# ST-Link-V1_0.net
KiCad netlist of a schematic drawn in Altium Designer
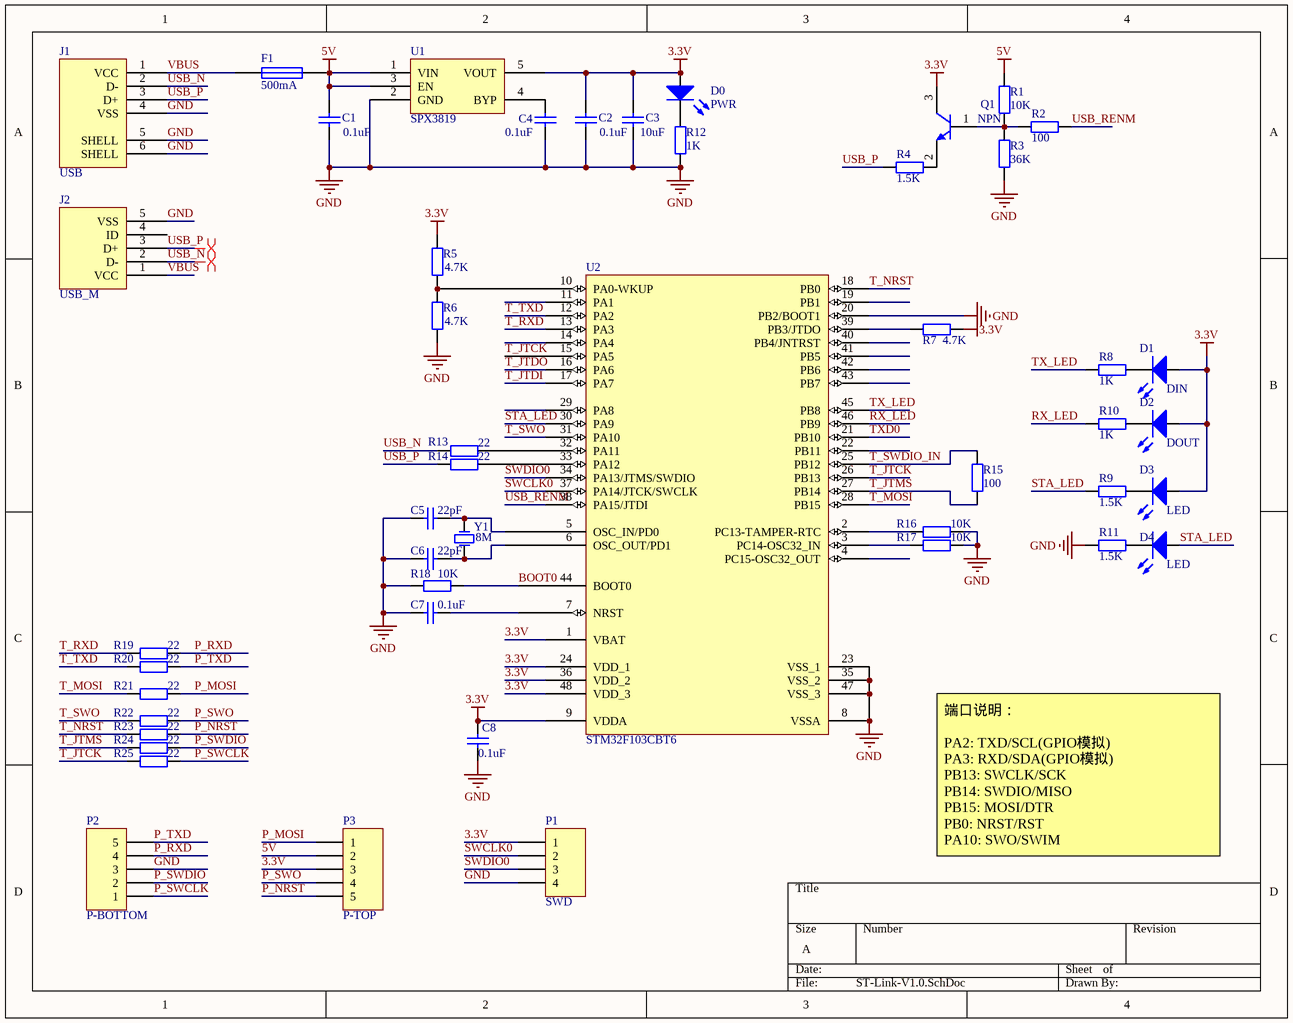
[diagram p0: ST-Link-V1.0.SchDoc]

(export (version "E")
  (design (tool "Eeschema 10.0.6"))
  (components
    (comp (ref "C1")
      (value "0.1uF")
      (footprint "C-0603")
      (description "Capacitor")
      (fields (field (name "Comment") "Cap") (field (name "PUBLISHER") "Altium Limited"))
      (libsource (lib "Miscellaneous Devices") (part "Cap"))
    )
    (comp (ref "C2")
      (value "0.1uF")
      (footprint "C-0603")
      (description "Capacitor")
      (fields (field (name "Comment") "Cap") (field (name "PUBLISHER") "Altium Limited"))
      (libsource (lib "Miscellaneous Devices") (part "Cap"))
    )
    (comp (ref "C3")
      (value "10uF")
      (footprint "C-0603")
      (description "Capacitor")
      (fields (field (name "Comment") "Cap") (field (name "PUBLISHER") "Altium Limited"))
      (libsource (lib "Miscellaneous Devices") (part "Cap"))
    )
    (comp (ref "C4")
      (value "0.1uF")
      (footprint "C-0603")
      (description "Capacitor")
      (fields (field (name "Comment") "Cap") (field (name "PUBLISHER") "Altium Limited"))
      (libsource (lib "Miscellaneous Devices") (part "Cap"))
    )
    (comp (ref "C5")
      (value "22pF")
      (footprint "C-0603")
      (fields (field (name "Comment") "Cap"))
      (libsource (lib "WK_PCB") (part "Cap"))
    )
    (comp (ref "C6")
      (value "22pF")
      (footprint "C-0603")
      (fields (field (name "Comment") "Cap"))
      (libsource (lib "WK_PCB") (part "Cap"))
    )
    (comp (ref "C7")
      (value "0.1uF")
      (footprint "C-0603")
      (fields (field (name "Comment") "Cap"))
      (libsource (lib "WK_PCB") (part "Cap"))
    )
    (comp (ref "C8")
      (value "0.1uF")
      (footprint "C-0603")
      (description "Capacitor")
      (fields (field (name "Comment") "Cap") (field (name "PUBLISHER") "Altium Limited"))
      (libsource (lib "Miscellaneous Devices") (part "Cap"))
    )
    (comp (ref "D0")
      (value "PWR")
      (footprint "SMT_LED_0603")
      (description "Typical RED, GREEN, YELLOW, AMBER GaAs LED")
      (fields (field (name "PUBLISHER") "Altium Limited"))
      (libsource (lib "ST-Link-V2.2") (part "LED2"))
    )
    (comp (ref "D1")
      (value "DIN")
      (footprint "SMT_LED_0603")
      (description "Typical RED, GREEN, YELLOW, AMBER GaAs LED")
      (fields (field (name "PUBLISHER") "Altium Limited"))
      (libsource (lib "ST-Link-V2.2") (part "LED2"))
    )
    (comp (ref "D2")
      (value "DOUT")
      (footprint "SMT_LED_0603")
      (description "Typical RED, GREEN, YELLOW, AMBER GaAs LED")
      (fields (field (name "PUBLISHER") "Altium Limited"))
      (libsource (lib "ST-Link-V2.2") (part "LED2"))
    )
    (comp (ref "D3")
      (value "LED")
      (footprint "SMT_LED_0603")
      (description "Typical RED, GREEN, YELLOW, AMBER GaAs LED")
      (fields (field (name "PUBLISHER") "Altium Limited"))
      (libsource (lib "ST-Link-V2.2") (part "LED2"))
    )
    (comp (ref "D4")
      (value "LED")
      (footprint "SMT_LED_0603")
      (description "Typical RED, GREEN, YELLOW, AMBER GaAs LED")
      (fields (field (name "PUBLISHER") "Altium Limited"))
      (libsource (lib "ST-Link-V2.2") (part "LED2"))
    )
    (comp (ref "F1")
      (value "500mA")
      (footprint "0805-1")
      (description "保险丝")
      (fields (field (name "Comment") "Fuse1"))
      (libsource (lib "ST-Link-V2.2") (part "Fuse1"))
    )
    (comp (ref "J1")
      (value "USB")
      (footprint "USB-B")
      (description "USB接口")
      (libsource (lib "HDR_Fszhang") (part "USB"))
    )
    (comp (ref "J2")
      (value "USB_M")
      (footprint "USB_MICRO_5S_B")
      (description "Micro/Mini USB")
      (libsource (lib "HDR_Fszhang") (part "USB_M"))
    )
    (comp (ref "P1")
      (value "SWD")
      (footprint "SIP4-1.27")
      (description "Header, 4-Pin")
      (fields (field (name "PUBLISHER") "Altium Limited"))
      (libsource (lib "Miscellaneous Connectors") (part "Header 4"))
    )
    (comp (ref "P2")
      (value "P-BOTTOM")
      (footprint "HEADER_5")
      (description "Header, 5-Pin")
      (fields (field (name "PUBLISHER") "Altium Limited"))
      (libsource (lib "Miscellaneous Connectors") (part "Header 5"))
    )
    (comp (ref "P3")
      (value "P-TOP")
      (footprint "HEADER_5")
      (description "Header, 5-Pin")
      (fields (field (name "PUBLISHER") "Altium Limited"))
      (libsource (lib "") (part "Header 5_1"))
    )
    (comp (ref "Q1")
      (value "NPN")
      (footprint "SOT23-3")
      (description "贴片三极管")
      (fields (field (name "PUBLISHER") "Altium Limited"))
      (libsource (lib "Fszhang") (part "NPN1"))
    )
    (comp (ref "R1")
      (value "10K")
      (footprint "0603-1")
      (description "贴片电阻")
      (fields (field (name "Comment") "Res1") (field (name "PUBLISHER") "Altium Limited"))
      (libsource (lib "Fszhang") (part "Res1"))
    )
    (comp (ref "R2")
      (value "100")
      (footprint "0603-1")
      (description "贴片电阻")
      (fields (field (name "Comment") "Res1") (field (name "PUBLISHER") "Altium Limited"))
      (libsource (lib "") (part "Res1_1"))
    )
    (comp (ref "R3")
      (value "36K")
      (footprint "0603-1")
      (description "贴片电阻")
      (fields (field (name "Comment") "Res1") (field (name "PUBLISHER") "Altium Limited"))
      (libsource (lib "Fszhang") (part "Res1"))
    )
    (comp (ref "R4")
      (value "1.5K")
      (footprint "0603-1")
      (description "贴片电阻")
      (fields (field (name "Comment") "Res1") (field (name "PUBLISHER") "Altium Limited"))
      (libsource (lib "") (part "Res1_2"))
    )
    (comp (ref "R5")
      (value "4.7K")
      (footprint "0603-1")
      (description "Resistor")
      (fields (field (name "Comment") "Res2") (field (name "PUBLISHER") "Altium Limited"))
      (libsource (lib "") (part "Res2_2"))
    )
    (comp (ref "R6")
      (value "4.7K")
      (footprint "0603-1")
      (description "Resistor")
      (fields (field (name "Comment") "Res2") (field (name "PUBLISHER") "Altium Limited"))
      (libsource (lib "") (part "Res2_2"))
    )
    (comp (ref "R7")
      (value "4.7K")
      (footprint "0603-1")
      (description "Resistor")
      (fields (field (name "Comment") "Res2") (field (name "PUBLISHER") "Altium Limited"))
      (libsource (lib "Miscellaneous Devices") (part "Res2"))
    )
    (comp (ref "R8")
      (value "1K")
      (footprint "0603-1")
      (description "Resistor")
      (fields (field (name "Comment") "Res2") (field (name "PUBLISHER") "Altium Limited"))
      (libsource (lib "Miscellaneous Devices") (part "Res2"))
    )
    (comp (ref "R9")
      (value "1.5K")
      (footprint "0603-1")
      (description "Resistor")
      (fields (field (name "Comment") "Res2") (field (name "PUBLISHER") "Altium Limited"))
      (libsource (lib "") (part "Res2_1"))
    )
    (comp (ref "R10")
      (value "1K")
      (footprint "0603-1")
      (description "Resistor")
      (fields (field (name "Comment") "Res2") (field (name "PUBLISHER") "Altium Limited"))
      (libsource (lib "Miscellaneous Devices") (part "Res2"))
    )
    (comp (ref "R11")
      (value "1.5K")
      (footprint "0603-1")
      (description "Resistor")
      (fields (field (name "Comment") "Res2") (field (name "PUBLISHER") "Altium Limited"))
      (libsource (lib "") (part "Res2_2"))
    )
    (comp (ref "R12")
      (value "1K")
      (footprint "0603-1")
      (description "Resistor")
      (fields (field (name "Comment") "Res2") (field (name "PUBLISHER") "Altium Limited"))
      (libsource (lib "") (part "Res2_2"))
    )
    (comp (ref "R13")
      (value "22")
      (footprint "0603-1")
      (description "Resistor")
      (fields (field (name "Comment") "Res2") (field (name "PUBLISHER") "Altium Limited"))
      (libsource (lib "Miscellaneous Devices") (part "Res2"))
    )
    (comp (ref "R14")
      (value "22")
      (footprint "0603-1")
      (description "Resistor")
      (fields (field (name "Comment") "Res2") (field (name "PUBLISHER") "Altium Limited"))
      (libsource (lib "Miscellaneous Devices") (part "Res2"))
    )
    (comp (ref "R15")
      (value "100")
      (footprint "0603-1")
      (description "Resistor")
      (fields (field (name "Comment") "Res2") (field (name "PUBLISHER") "Altium Limited"))
      (libsource (lib "") (part "Res2_2"))
    )
    (comp (ref "R16")
      (value "10K")
      (footprint "0603-1")
      (description "贴片电阻")
      (fields (field (name "Comment") "Res1") (field (name "PUBLISHER") "Altium Limited"))
      (libsource (lib "") (part "Res1_1"))
    )
    (comp (ref "R17")
      (value "10K")
      (footprint "0603-1")
      (description "贴片电阻")
      (fields (field (name "Comment") "Res1") (field (name "PUBLISHER") "Altium Limited"))
      (libsource (lib "") (part "Res1_1"))
    )
    (comp (ref "R18")
      (value "10K")
      (footprint "0603-1")
      (description "Resistor")
      (fields (field (name "Comment") "Res2") (field (name "PUBLISHER") "Altium Limited"))
      (libsource (lib "Miscellaneous Devices") (part "Res2"))
    )
    (comp (ref "R19")
      (value "22")
      (footprint "0603-1")
      (description "Resistor")
      (fields (field (name "Comment") "Res2") (field (name "PUBLISHER") "Altium Limited"))
      (libsource (lib "Miscellaneous Devices") (part "Res2"))
    )
    (comp (ref "R20")
      (value "22")
      (footprint "0603-1")
      (description "Resistor")
      (fields (field (name "Comment") "Res2") (field (name "PUBLISHER") "Altium Limited"))
      (libsource (lib "Miscellaneous Devices") (part "Res2"))
    )
    (comp (ref "R21")
      (value "22")
      (footprint "0603-1")
      (description "Resistor")
      (fields (field (name "Comment") "Res2") (field (name "PUBLISHER") "Altium Limited"))
      (libsource (lib "Miscellaneous Devices") (part "Res2"))
    )
    (comp (ref "R22")
      (value "22")
      (footprint "0603-1")
      (description "Resistor")
      (fields (field (name "Comment") "Res2") (field (name "PUBLISHER") "Altium Limited"))
      (libsource (lib "Miscellaneous Devices") (part "Res2"))
    )
    (comp (ref "R23")
      (value "22")
      (footprint "0603-1")
      (description "Resistor")
      (fields (field (name "Comment") "Res2") (field (name "PUBLISHER") "Altium Limited"))
      (libsource (lib "Miscellaneous Devices") (part "Res2"))
    )
    (comp (ref "R24")
      (value "22")
      (footprint "0603-1")
      (description "Resistor")
      (fields (field (name "Comment") "Res2") (field (name "PUBLISHER") "Altium Limited"))
      (libsource (lib "Miscellaneous Devices") (part "Res2"))
    )
    (comp (ref "R25")
      (value "22")
      (footprint "0603-1")
      (description "Resistor")
      (fields (field (name "Comment") "Res2") (field (name "PUBLISHER") "Altium Limited"))
      (libsource (lib "Miscellaneous Devices") (part "Res2"))
    )
    (comp (ref "U1") (value "SPX3819") (footprint "SOT23-5") (libsource (lib "Schlib1") (part "SPX3819")))
    (comp (ref "U2")
      (value "STM32F103CBT6")
      (footprint "LQFP48_N")
      (description "STM32 ARM-based 32-bit MCU with 64 Kbytes Flash, 48-pin LQFP, Industrial Temperature")
      (fields (field (name "PUBLISHER") "Altium Limited"))
      (libsource (lib "ST Microcontroller 32-Bit STM32") (part "STM32F103C8T6"))
    )
    (comp (ref "Y1")
      (value "8M")
      (footprint "XAL5032 2-Leads")
      (description "Crystal Oscillator")
      (fields
        (field (name "MANUFACTURER") "Generic Components")
        (field (name "PUBLISHER") "Altium Hobart Technology Centre")
      )
      (libsource (lib "*") (part "XTAL"))
    )
  )
  (nets
    (net (code "1") (name "/BOOT0") (class "Default")
      (node (ref "R18") (pin "2") (pinfunction "2_2") (pintype "passive"))
      (node (ref "U2") (pin "44") (pinfunction "BOOT0_44") (pintype "passive"))
    )
    (net (code "2") (name "/P_MOSI") (class "Default")
      (node (ref "P3") (pin "1") (pinfunction "1_1") (pintype "passive"))
      (node (ref "R21") (pin "2") (pinfunction "2_2") (pintype "passive"))
    )
    (net (code "3") (name "/P_NRST") (class "Default")
      (node (ref "P3") (pin "5") (pinfunction "5_5") (pintype "passive"))
      (node (ref "R23") (pin "2") (pinfunction "2_2") (pintype "passive"))
    )
    (net (code "4") (name "/P_RXD") (class "Default")
      (node (ref "P2") (pin "4") (pinfunction "4_4") (pintype "passive"))
      (node (ref "R19") (pin "2") (pinfunction "2_2") (pintype "passive"))
    )
    (net (code "5") (name "/P_SWCLK") (class "Default")
      (node (ref "P2") (pin "1") (pinfunction "1_1") (pintype "passive"))
      (node (ref "R25") (pin "2") (pinfunction "2_2") (pintype "passive"))
    )
    (net (code "6") (name "/P_SWDIO") (class "Default")
      (node (ref "P2") (pin "2") (pinfunction "2_2") (pintype "passive"))
      (node (ref "R24") (pin "2") (pinfunction "2_2") (pintype "passive"))
    )
    (net (code "7") (name "/P_SWO") (class "Default")
      (node (ref "P3") (pin "4") (pinfunction "4_4") (pintype "passive"))
      (node (ref "R22") (pin "2") (pinfunction "2_2") (pintype "passive"))
    )
    (net (code "8") (name "/P_TXD") (class "Default")
      (node (ref "P2") (pin "5") (pinfunction "5_5") (pintype "passive"))
      (node (ref "R20") (pin "2") (pinfunction "2_2") (pintype "passive"))
    )
    (net (code "9") (name "/RX_LED") (class "Default")
      (node (ref "R10") (pin "1") (pinfunction "1_1") (pintype "passive"))
      (node (ref "U2") (pin "46") (pinfunction "PB9_46") (pintype "bidirectional"))
    )
    (net (code "10") (name "/STA_LED") (class "Default")
      (node (ref "D4") (pin "1") (pinfunction "A_1") (pintype "passive"))
      (node (ref "R9") (pin "2") (pinfunction "2_2") (pintype "passive"))
      (node (ref "U2") (pin "30") (pinfunction "PA9_30") (pintype "bidirectional"))
    )
    (net (code "11") (name "/SWCLK0") (class "Default")
      (node (ref "P1") (pin "2") (pinfunction "2_2") (pintype "passive"))
      (node (ref "U2") (pin "37") (pinfunction "PA14/JTCK/SWCLK_37") (pintype "bidirectional"))
    )
    (net (code "12") (name "/SWDIO0") (class "Default")
      (node (ref "P1") (pin "3") (pinfunction "3_3") (pintype "passive"))
      (node (ref "U2") (pin "34") (pinfunction "PA13/JTMS/SWDIO_34") (pintype "bidirectional"))
    )
    (net (code "13") (name "/TXD0") (class "Default")
      (node (ref "U2") (pin "21") (pinfunction "PB10_21") (pintype "bidirectional"))
    )
    (net (code "14") (name "/TX_LED") (class "Default")
      (node (ref "R8") (pin "1") (pinfunction "1_1") (pintype "passive"))
      (node (ref "U2") (pin "45") (pinfunction "PB8_45") (pintype "bidirectional"))
    )
    (net (code "15") (name "/T_JTCK") (class "Default")
      (node (ref "R25") (pin "1") (pinfunction "1_1") (pintype "passive"))
      (node (ref "U2") (pin "15") (pinfunction "PA5_15") (pintype "bidirectional"))
      (node (ref "U2") (pin "26") (pinfunction "PB13_26") (pintype "bidirectional"))
    )
    (net (code "16") (name "/T_JTDI") (class "Default")
      (node (ref "U2") (pin "17") (pinfunction "PA7_17") (pintype "bidirectional"))
    )
    (net (code "17") (name "/T_JTDO") (class "Default")
      (node (ref "U2") (pin "16") (pinfunction "PA6_16") (pintype "bidirectional"))
    )
    (net (code "18") (name "/T_JTMS") (class "Default")
      (node (ref "R15") (pin "1") (pinfunction "1_1") (pintype "passive"))
      (node (ref "R24") (pin "1") (pinfunction "1_1") (pintype "passive"))
      (node (ref "U2") (pin "27") (pinfunction "PB14_27") (pintype "bidirectional"))
    )
    (net (code "19") (name "/T_MOSI") (class "Default")
      (node (ref "R21") (pin "1") (pinfunction "1_1") (pintype "passive"))
      (node (ref "U2") (pin "28") (pinfunction "PB15_28") (pintype "bidirectional"))
    )
    (net (code "20") (name "/T_NRST") (class "Default")
      (node (ref "R23") (pin "1") (pinfunction "1_1") (pintype "passive"))
      (node (ref "U2") (pin "18") (pinfunction "PB0_18") (pintype "bidirectional"))
    )
    (net (code "21") (name "/T_RXD") (class "Default")
      (node (ref "R19") (pin "1") (pinfunction "1_1") (pintype "passive"))
      (node (ref "U2") (pin "13") (pinfunction "PA3_13") (pintype "bidirectional"))
    )
    (net (code "22") (name "/T_SWDIO_IN") (class "Default")
      (node (ref "R15") (pin "2") (pinfunction "2_2") (pintype "passive"))
      (node (ref "U2") (pin "25") (pinfunction "PB12_25") (pintype "bidirectional"))
    )
    (net (code "23") (name "/T_SWO") (class "Default")
      (node (ref "R22") (pin "1") (pinfunction "1_1") (pintype "passive"))
      (node (ref "U2") (pin "31") (pinfunction "PA10_31") (pintype "bidirectional"))
    )
    (net (code "24") (name "/T_TXD") (class "Default")
      (node (ref "R20") (pin "1") (pinfunction "1_1") (pintype "passive"))
      (node (ref "U2") (pin "12") (pinfunction "PA2_12") (pintype "bidirectional"))
    )
    (net (code "25") (name "/USB_N") (class "Default")
      (node (ref "J1") (pin "2") (pinfunction "D-_2") (pintype "passive"))
      (node (ref "J2") (pin "2") (pinfunction "D-_2") (pintype "passive"))
      (node (ref "R13") (pin "1") (pinfunction "1_1") (pintype "passive"))
    )
    (net (code "26") (name "/USB_P") (class "Default")
      (node (ref "J1") (pin "3") (pinfunction "D+_3") (pintype "passive"))
      (node (ref "J2") (pin "3") (pinfunction "D+_3") (pintype "passive"))
      (node (ref "R14") (pin "1") (pinfunction "1_1") (pintype "passive"))
      (node (ref "R4") (pin "2") (pinfunction "2_2") (pintype "passive"))
    )
    (net (code "27") (name "/USB_RENM") (class "Default")
      (node (ref "R2") (pin "2") (pinfunction "2_2") (pintype "passive"))
      (node (ref "U2") (pin "38") (pinfunction "PA15/JTDI_38") (pintype "bidirectional"))
    )
    (net (code "28") (name "/VBUS") (class "Default")
      (node (ref "F1") (pin "1") (pinfunction "1_1") (pintype "passive"))
      (node (ref "J1") (pin "1") (pinfunction "VCC_1") (pintype "passive"))
      (node (ref "J2") (pin "1") (pinfunction "VCC_1") (pintype "passive"))
    )
    (net (code "29") (name "3.3V") (class "Default")
      (node (ref "C2") (pin "2") (pinfunction "2_2") (pintype "passive"))
      (node (ref "C3") (pin "2") (pinfunction "2_2") (pintype "passive"))
      (node (ref "C8") (pin "2") (pinfunction "2_2") (pintype "passive"))
      (node (ref "D0") (pin "1") (pinfunction "A_1") (pintype "passive"))
      (node (ref "D1") (pin "1") (pinfunction "A_1") (pintype "passive"))
      (node (ref "D2") (pin "1") (pinfunction "A_1") (pintype "passive"))
      (node (ref "D3") (pin "1") (pinfunction "A_1") (pintype "passive"))
      (node (ref "P1") (pin "1") (pinfunction "1_1") (pintype "passive"))
      (node (ref "P3") (pin "3") (pinfunction "3_3") (pintype "passive"))
      (node (ref "Q1") (pin "3") (pinfunction "C_3") (pintype "passive"))
      (node (ref "R5") (pin "2") (pinfunction "2_2") (pintype "passive"))
      (node (ref "R7") (pin "2") (pinfunction "2_2") (pintype "passive"))
      (node (ref "U1") (pin "5") (pinfunction "VOUT_5") (pintype "passive"))
      (node (ref "U2") (pin "1") (pinfunction "VBAT_1") (pintype "power_in"))
      (node (ref "U2") (pin "24") (pinfunction "VDD_1_24") (pintype "power_in"))
      (node (ref "U2") (pin "36") (pinfunction "VDD_2_36") (pintype "power_in"))
      (node (ref "U2") (pin "48") (pinfunction "VDD_3_48") (pintype "power_in"))
      (node (ref "U2") (pin "9") (pinfunction "VDDA_9") (pintype "power_in"))
    )
    (net (code "30") (name "5V") (class "Default")
      (node (ref "C1") (pin "2") (pinfunction "2_2") (pintype "passive"))
      (node (ref "F1") (pin "2") (pinfunction "2_2") (pintype "passive"))
      (node (ref "P3") (pin "2") (pinfunction "2_2") (pintype "passive"))
      (node (ref "R1") (pin "1") (pinfunction "1_1") (pintype "passive"))
      (node (ref "U1") (pin "1") (pinfunction "VIN_1") (pintype "passive"))
      (node (ref "U1") (pin "3") (pinfunction "EN_3") (pintype "passive"))
    )
    (net (code "31") (name "GND") (class "Default")
      (node (ref "C1") (pin "1") (pinfunction "1_1") (pintype "passive"))
      (node (ref "C2") (pin "1") (pinfunction "1_1") (pintype "passive"))
      (node (ref "C3") (pin "1") (pinfunction "1_1") (pintype "passive"))
      (node (ref "C4") (pin "1") (pinfunction "1_1") (pintype "passive"))
      (node (ref "C5") (pin "1") (pinfunction "1_1") (pintype "passive"))
      (node (ref "C6") (pin "1") (pinfunction "1_1") (pintype "passive"))
      (node (ref "C7") (pin "1") (pinfunction "1_1") (pintype "passive"))
      (node (ref "C8") (pin "1") (pinfunction "1_1") (pintype "passive"))
      (node (ref "J1") (pin "4") (pinfunction "VSS_4") (pintype "passive"))
      (node (ref "J1") (pin "5") (pinfunction "SHELL_5") (pintype "passive"))
      (node (ref "J1") (pin "6") (pinfunction "SHELL_6") (pintype "passive"))
      (node (ref "J2") (pin "5") (pinfunction "VSS_5") (pintype "passive"))
      (node (ref "P1") (pin "4") (pinfunction "4_4") (pintype "passive"))
      (node (ref "P2") (pin "3") (pinfunction "3_3") (pintype "passive"))
      (node (ref "R11") (pin "1") (pinfunction "1_1") (pintype "passive"))
      (node (ref "R12") (pin "1") (pinfunction "1_1") (pintype "passive"))
      (node (ref "R16") (pin "2") (pinfunction "2_2") (pintype "passive"))
      (node (ref "R17") (pin "2") (pinfunction "2_2") (pintype "passive"))
      (node (ref "R18") (pin "1") (pinfunction "1_1") (pintype "passive"))
      (node (ref "R3") (pin "2") (pinfunction "2_2") (pintype "passive"))
      (node (ref "R6") (pin "1") (pinfunction "1_1") (pintype "passive"))
      (node (ref "U1") (pin "2") (pinfunction "GND_2") (pintype "passive"))
      (node (ref "U2") (pin "20") (pinfunction "PB2/BOOT1_20") (pintype "bidirectional"))
      (node (ref "U2") (pin "23") (pinfunction "VSS_1_23") (pintype "power_in"))
      (node (ref "U2") (pin "35") (pinfunction "VSS_2_35") (pintype "power_in"))
      (node (ref "U2") (pin "47") (pinfunction "VSS_3_47") (pintype "power_in"))
      (node (ref "U2") (pin "8") (pinfunction "VSSA_8") (pintype "power_in"))
    )
    (net (code "32") (name "Net-(D0-K)") (class "Default")
      (node (ref "D0") (pin "2") (pinfunction "K_2") (pintype "passive"))
      (node (ref "R12") (pin "2") (pinfunction "2_2") (pintype "passive"))
    )
    (net (code "33") (name "Net-(D1-K)") (class "Default")
      (node (ref "D1") (pin "2") (pinfunction "K_2") (pintype "passive"))
      (node (ref "R8") (pin "2") (pinfunction "2_2") (pintype "passive"))
    )
    (net (code "34") (name "Net-(D2-K)") (class "Default")
      (node (ref "D2") (pin "2") (pinfunction "K_2") (pintype "passive"))
      (node (ref "R10") (pin "2") (pinfunction "2_2") (pintype "passive"))
    )
    (net (code "35") (name "Net-(D3-K)") (class "Default")
      (node (ref "D3") (pin "2") (pinfunction "K_2") (pintype "passive"))
      (node (ref "R9") (pin "1") (pinfunction "1_1") (pintype "passive"))
    )
    (net (code "36") (name "Net-(D4-K)") (class "Default")
      (node (ref "D4") (pin "2") (pinfunction "K_2") (pintype "passive"))
      (node (ref "R11") (pin "2") (pinfunction "2_2") (pintype "passive"))
    )
    (net (code "37") (name "Net-(Q1-B)") (class "Default")
      (node (ref "Q1") (pin "1") (pinfunction "B_1") (pintype "passive"))
      (node (ref "R1") (pin "2") (pinfunction "2_2") (pintype "passive"))
      (node (ref "R2") (pin "1") (pinfunction "1_1") (pintype "passive"))
      (node (ref "R3") (pin "1") (pinfunction "1_1") (pintype "passive"))
    )
    (net (code "38") (name "Net-(Q1-E)") (class "Default")
      (node (ref "Q1") (pin "2") (pinfunction "E_2") (pintype "passive"))
      (node (ref "R4") (pin "1") (pinfunction "1_1") (pintype "passive"))
    )
    (net (code "39") (name "Net-(U1-BYP)") (class "Default")
      (node (ref "C4") (pin "2") (pinfunction "2_2") (pintype "passive"))
      (node (ref "U1") (pin "4") (pinfunction "BYP_4") (pintype "passive"))
    )
    (net (code "40") (name "Net-(U2-NRST)") (class "Default")
      (node (ref "C7") (pin "2") (pinfunction "2_2") (pintype "passive"))
      (node (ref "U2") (pin "7") (pinfunction "NRST_7") (pintype "bidirectional"))
    )
    (net (code "41") (name "Net-(U2-OSC_IN{slash}PD0)") (class "Default")
      (node (ref "C5") (pin "2") (pinfunction "2_2") (pintype "passive"))
      (node (ref "U2") (pin "5") (pinfunction "OSC_IN/PD0_5") (pintype "passive"))
      (node (ref "Y1") (pin "1") (pinfunction "OSC1_1") (pintype "passive"))
    )
    (net (code "42") (name "Net-(U2-OSC_OUT{slash}PD1)") (class "Default")
      (node (ref "C6") (pin "2") (pinfunction "2_2") (pintype "passive"))
      (node (ref "U2") (pin "6") (pinfunction "OSC_OUT/PD1_6") (pintype "passive"))
      (node (ref "Y1") (pin "2") (pinfunction "OSC2_2") (pintype "passive"))
    )
    (net (code "43") (name "Net-(U2-PA0-WKUP)") (class "Default")
      (node (ref "R5") (pin "1") (pinfunction "1_1") (pintype "passive"))
      (node (ref "R6") (pin "2") (pinfunction "2_2") (pintype "passive"))
      (node (ref "U2") (pin "10") (pinfunction "PA0-WKUP_10") (pintype "bidirectional"))
    )
    (net (code "44") (name "Net-(U2-PA11)") (class "Default")
      (node (ref "R13") (pin "2") (pinfunction "2_2") (pintype "passive"))
      (node (ref "U2") (pin "32") (pinfunction "PA11_32") (pintype "bidirectional"))
    )
    (net (code "45") (name "Net-(U2-PA12)") (class "Default")
      (node (ref "R14") (pin "2") (pinfunction "2_2") (pintype "passive"))
      (node (ref "U2") (pin "33") (pinfunction "PA12_33") (pintype "bidirectional"))
    )
    (net (code "46") (name "Net-(U2-PB3{slash}JTDO)") (class "Default")
      (node (ref "R7") (pin "1") (pinfunction "1_1") (pintype "passive"))
      (node (ref "U2") (pin "39") (pinfunction "PB3/JTDO_39") (pintype "bidirectional"))
    )
    (net (code "47") (name "Net-(U2-PC13-TAMPER-RTC)") (class "Default")
      (node (ref "R16") (pin "1") (pinfunction "1_1") (pintype "passive"))
      (node (ref "U2") (pin "2") (pinfunction "PC13-TAMPER-RTC_2") (pintype "bidirectional"))
    )
    (net (code "48") (name "Net-(U2-PC14-OSC32_IN)") (class "Default")
      (node (ref "R17") (pin "1") (pinfunction "1_1") (pintype "passive"))
      (node (ref "U2") (pin "3") (pinfunction "PC14-OSC32_IN_3") (pintype "bidirectional"))
    )
    (net (code "49") (name "unconnected-(J2-ID-Pad4)") (class "Default")
      (node (ref "J2") (pin "4") (pinfunction "ID_4") (pintype "passive"))
    )
    (net (code "50") (name "unconnected-(U2-PA1-Pad11)") (class "Default")
      (node (ref "U2") (pin "11") (pinfunction "PA1_11") (pintype "bidirectional"))
    )
    (net (code "51") (name "unconnected-(U2-PA4-Pad14)") (class "Default")
      (node (ref "U2") (pin "14") (pinfunction "PA4_14") (pintype "bidirectional"))
    )
    (net (code "52") (name "unconnected-(U2-PA8-Pad29)") (class "Default")
      (node (ref "U2") (pin "29") (pinfunction "PA8_29") (pintype "bidirectional"))
    )
    (net (code "53") (name "unconnected-(U2-PB1-Pad19)") (class "Default")
      (node (ref "U2") (pin "19") (pinfunction "PB1_19") (pintype "bidirectional"))
    )
    (net (code "54") (name "unconnected-(U2-PB4{slash}JNTRST-Pad40)") (class "Default")
      (node (ref "U2") (pin "40") (pinfunction "PB4/JNTRST_40") (pintype "bidirectional"))
    )
    (net (code "55") (name "unconnected-(U2-PB5-Pad41)") (class "Default")
      (node (ref "U2") (pin "41") (pinfunction "PB5_41") (pintype "bidirectional"))
    )
    (net (code "56") (name "unconnected-(U2-PB6-Pad42)") (class "Default")
      (node (ref "U2") (pin "42") (pinfunction "PB6_42") (pintype "bidirectional"))
    )
    (net (code "57") (name "unconnected-(U2-PB7-Pad43)") (class "Default")
      (node (ref "U2") (pin "43") (pinfunction "PB7_43") (pintype "bidirectional"))
    )
    (net (code "58") (name "unconnected-(U2-PB11-Pad22)") (class "Default")
      (node (ref "U2") (pin "22") (pinfunction "PB11_22") (pintype "bidirectional"))
    )
    (net (code "59") (name "unconnected-(U2-PC15-OSC32_OUT-Pad4)") (class "Default")
      (node (ref "U2") (pin "4") (pinfunction "PC15-OSC32_OUT_4") (pintype "bidirectional"))
    )
  )
)
